# PennyMan_Ard_R3_Shield_v7.net
KiCad netlist of a schematic drawn in EAGLE
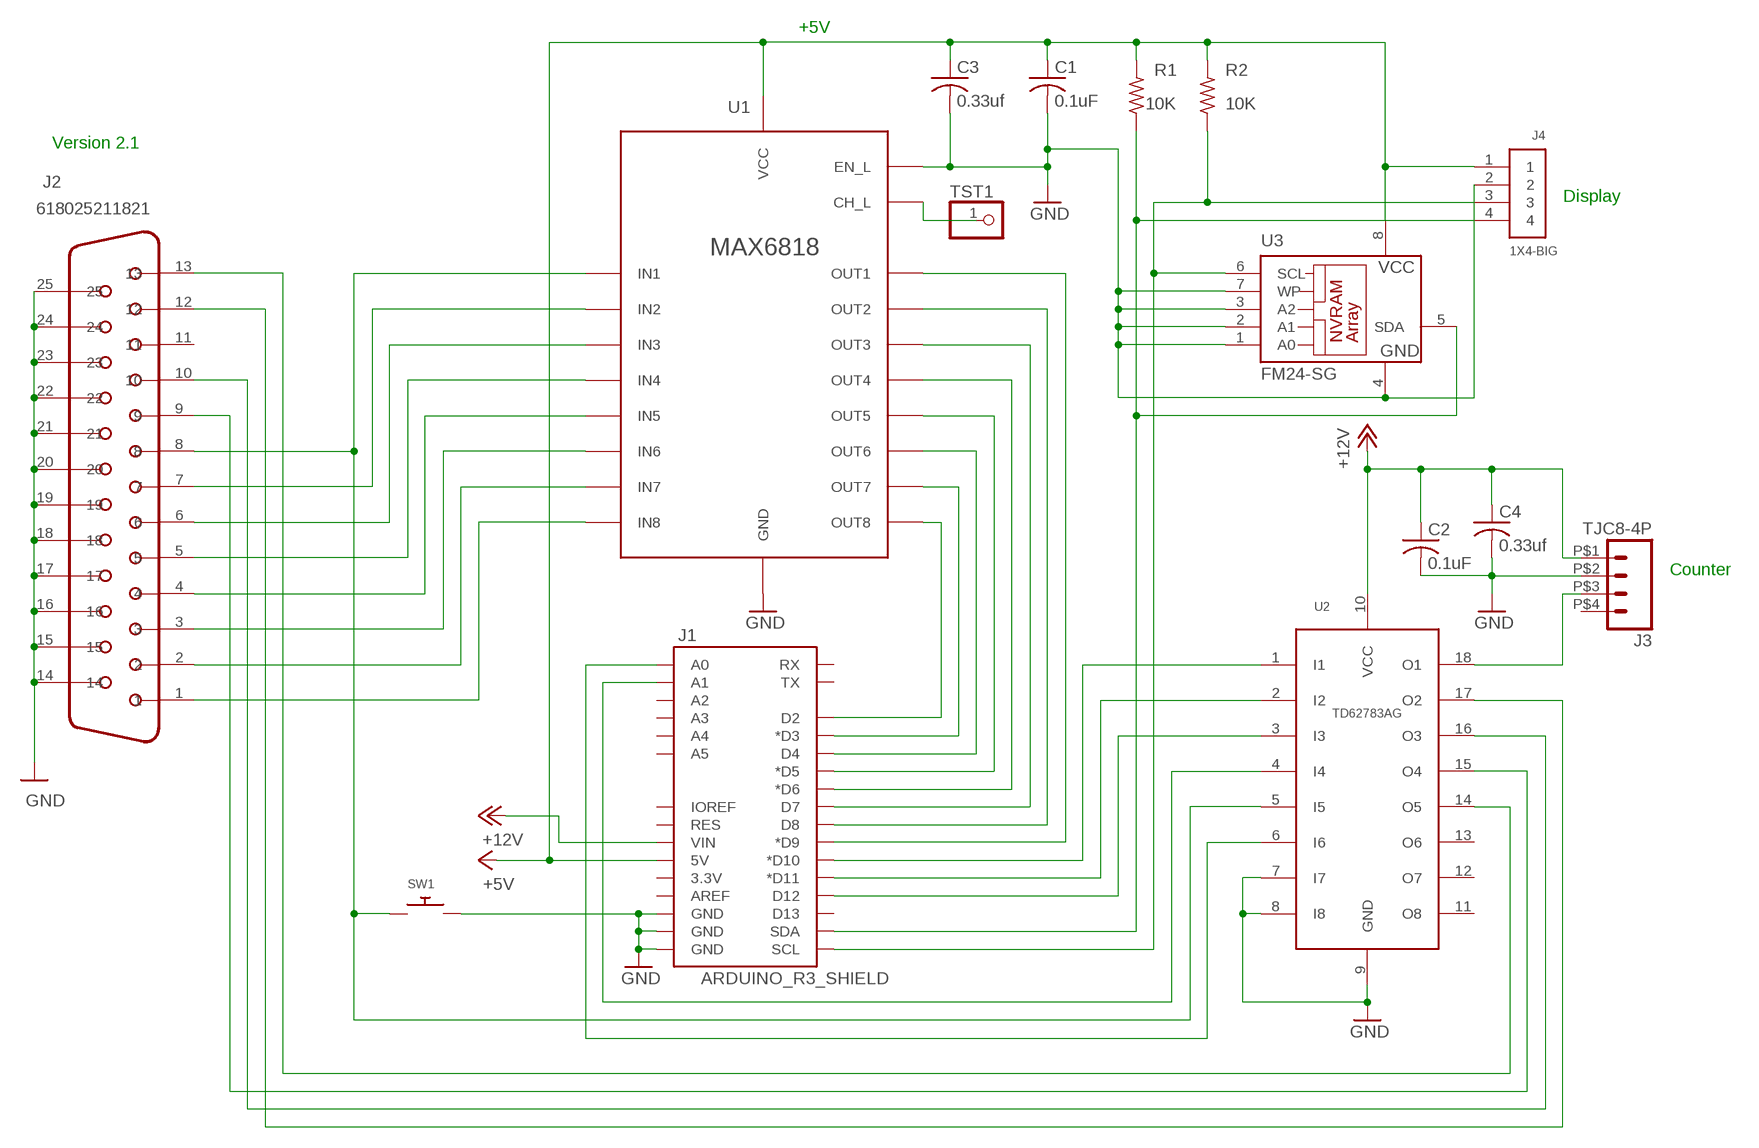
[diagram p0: schematic, sheet 1]

(export (version "E")
  (design (tool "Eeschema 10.0.6"))
  (components
    (comp (ref "C1")
      (value "0.1uF")
      (footprint "eagle-import:C0805")
      (libsource (lib "eagle-import") (part "C-USC0805"))
    )
    (comp (ref "C2")
      (value "0.1uF")
      (footprint "eagle-import:C0805")
      (libsource (lib "eagle-import") (part "C-USC0805"))
    )
    (comp (ref "C3")
      (value "0.33uf")
      (footprint "eagle-import:C1206")
      (libsource (lib "eagle-import") (part "C-USC1206"))
    )
    (comp (ref "C4")
      (value "0.33uf")
      (footprint "eagle-import:C1206")
      (libsource (lib "eagle-import") (part "C-USC1206"))
    )
    (comp (ref "J1")
      (value "ARDUINO_R3_SHIELD")
      (footprint "eagle-import:UNO_R3_SHIELD")
      (libsource (lib "eagle-import") (part "ARDUINO_R3_SHIELD"))
    )
    (comp (ref "J2")
      (value "618025211821")
      (footprint "eagle-import:618025211821")
      (libsource (lib "eagle-import") (part "618025211821"))
    )
    (comp (ref "J3")
      (value "TJC8-4P")
      (footprint "eagle-import:TJC8-4P")
      (libsource (lib "eagle-import") (part "TJC8-4P"))
    )
    (comp (ref "J4")
      (value "1X4-BIG")
      (footprint "eagle-import:1X04-BIG")
      (libsource (lib "eagle-import") (part "1X4-BIG"))
    )
    (comp (ref "R1")
      (value "10K")
      (footprint "eagle-import:R0805")
      (libsource (lib "eagle-import") (part "R-US_R0805"))
    )
    (comp (ref "R2")
      (value "10K")
      (footprint "eagle-import:R0805")
      (libsource (lib "eagle-import") (part "R-US_R0805"))
    )
    (comp (ref "SW1")
      (value "SWITCH_PUSHBUTTONEVQ-PE")
      (footprint "eagle-import:TACT_PANA-EVQ")
      (libsource (lib "eagle-import") (part "SWITCH_PUSHBUTTONEVQ-PE"))
    )
    (comp (ref "TST1")
      (value "PINHD-1X1")
      (footprint "eagle-import:1X01")
      (libsource (lib "eagle-import") (part "PINHD-1X1"))
    )
    (comp (ref "U1")
      (value "MAX6818")
      (footprint "eagle-import:SSOP20")
      (libsource (lib "eagle-import") (part "MAX6818"))
    )
    (comp (ref "U2")
      (value "TD62783AG")
      (footprint "eagle-import:SOP18")
      (libsource (lib "eagle-import") (part "TD62783AG"))
    )
    (comp (ref "U3")
      (value "FM24-SG")
      (footprint "eagle-import:SO8")
      (libsource (lib "eagle-import") (part "FM24-SG"))
    )
  )
  (nets
    (net (code "1") (name "+5V") (class "Default")
      (node (ref "C1") (pin "1") (pinfunction "1_1") (pintype "passive"))
      (node (ref "C3") (pin "1") (pinfunction "1_1") (pintype "passive"))
      (node (ref "J1") (pin "5V") (pinfunction "5V_5V") (pintype "bidirectional"))
      (node (ref "J4") (pin "1") (pinfunction "1_1") (pintype "bidirectional"))
      (node (ref "R1") (pin "2") (pinfunction "2_2") (pintype "passive"))
      (node (ref "R2") (pin "2") (pinfunction "2_2") (pintype "passive"))
      (node (ref "U1") (pin "VCC") (pinfunction "VCC_VCC") (pintype "bidirectional"))
      (node (ref "U3") (pin "8") (pinfunction "VCC_8") (pintype "power_in"))
    )
    (net (code "2") (name "+12V") (class "Default")
      (node (ref "C2") (pin "1") (pinfunction "1_1") (pintype "passive"))
      (node (ref "C4") (pin "1") (pinfunction "1_1") (pintype "passive"))
      (node (ref "J1") (pin "VIN") (pinfunction "VIN_VIN") (pintype "bidirectional"))
      (node (ref "J3") (pin "P$1") (pinfunction "1_P$1") (pintype "passive"))
      (node (ref "U2") (pin "10") (pinfunction "VCC_10") (pintype "bidirectional"))
    )
    (net (code "3") (name "GND") (class "Default")
      (node (ref "C1") (pin "2") (pinfunction "2_2") (pintype "passive"))
      (node (ref "C2") (pin "2") (pinfunction "2_2") (pintype "passive"))
      (node (ref "C3") (pin "2") (pinfunction "2_2") (pintype "passive"))
      (node (ref "C4") (pin "2") (pinfunction "2_2") (pintype "passive"))
      (node (ref "J1") (pin "GND@0") (pinfunction "GND_GND@0") (pintype "bidirectional"))
      (node (ref "J1") (pin "GND@1") (pinfunction "GND_GND@1") (pintype "bidirectional"))
      (node (ref "J1") (pin "GND@2") (pinfunction "GND_GND@2") (pintype "bidirectional"))
      (node (ref "J2") (pin "14") (pinfunction "14_14") (pintype "bidirectional"))
      (node (ref "J2") (pin "15") (pinfunction "15_15") (pintype "bidirectional"))
      (node (ref "J2") (pin "16") (pinfunction "16_16") (pintype "bidirectional"))
      (node (ref "J2") (pin "17") (pinfunction "17_17") (pintype "bidirectional"))
      (node (ref "J2") (pin "18") (pinfunction "18_18") (pintype "bidirectional"))
      (node (ref "J2") (pin "19") (pinfunction "19_19") (pintype "bidirectional"))
      (node (ref "J2") (pin "20") (pinfunction "20_20") (pintype "bidirectional"))
      (node (ref "J2") (pin "21") (pinfunction "21_21") (pintype "bidirectional"))
      (node (ref "J2") (pin "22") (pinfunction "22_22") (pintype "bidirectional"))
      (node (ref "J2") (pin "23") (pinfunction "23_23") (pintype "bidirectional"))
      (node (ref "J2") (pin "24") (pinfunction "24_24") (pintype "bidirectional"))
      (node (ref "J2") (pin "25") (pinfunction "25_25") (pintype "bidirectional"))
      (node (ref "J3") (pin "P$2") (pinfunction "2_P$2") (pintype "passive"))
      (node (ref "J4") (pin "2") (pinfunction "2_2") (pintype "bidirectional"))
      (node (ref "SW1") (pin "P$2") (pinfunction "P$2_P$2") (pintype "passive"))
      (node (ref "U1") (pin "EN_L") (pinfunction "EN_L_EN_L") (pintype "bidirectional"))
      (node (ref "U1") (pin "GND") (pinfunction "GND_GND") (pintype "bidirectional"))
      (node (ref "U2") (pin "7") (pinfunction "I7_7") (pintype "bidirectional"))
      (node (ref "U2") (pin "8") (pinfunction "I8_8") (pintype "bidirectional"))
      (node (ref "U2") (pin "9") (pinfunction "GND_9") (pintype "bidirectional"))
      (node (ref "U3") (pin "1") (pinfunction "A0_1") (pintype "passive"))
      (node (ref "U3") (pin "2") (pinfunction "A1_2") (pintype "passive"))
      (node (ref "U3") (pin "3") (pinfunction "A2_3") (pintype "passive"))
      (node (ref "U3") (pin "4") (pinfunction "GND_4") (pintype "power_in"))
      (node (ref "U3") (pin "7") (pinfunction "WP_7") (pintype "input"))
    )
    (net (code "4") (name "Net-(J1-*D3)") (class "Default")
      (node (ref "J1") (pin "D3") (pinfunction "*D3_D3") (pintype "bidirectional"))
      (node (ref "U1") (pin "OUT7") (pinfunction "OUT7_OUT7") (pintype "bidirectional"))
    )
    (net (code "5") (name "Net-(J1-*D5)") (class "Default")
      (node (ref "J1") (pin "D5") (pinfunction "*D5_D5") (pintype "bidirectional"))
      (node (ref "U1") (pin "OUT5") (pinfunction "OUT5_OUT5") (pintype "bidirectional"))
    )
    (net (code "6") (name "Net-(J1-*D6)") (class "Default")
      (node (ref "J1") (pin "D6") (pinfunction "*D6_D6") (pintype "bidirectional"))
      (node (ref "U1") (pin "OUT4") (pinfunction "OUT4_OUT4") (pintype "bidirectional"))
    )
    (net (code "7") (name "Net-(J1-*D9)") (class "Default")
      (node (ref "J1") (pin "D9") (pinfunction "*D9_D9") (pintype "bidirectional"))
      (node (ref "U1") (pin "OUT1") (pinfunction "OUT1_OUT1") (pintype "bidirectional"))
    )
    (net (code "8") (name "Net-(J1-*D10)") (class "Default")
      (node (ref "J1") (pin "D10") (pinfunction "*D10_D10") (pintype "bidirectional"))
      (node (ref "U2") (pin "1") (pinfunction "I1_1") (pintype "bidirectional"))
    )
    (net (code "9") (name "Net-(J1-*D11)") (class "Default")
      (node (ref "J1") (pin "D11") (pinfunction "*D11_D11") (pintype "bidirectional"))
      (node (ref "U2") (pin "2") (pinfunction "I2_2") (pintype "bidirectional"))
    )
    (net (code "10") (name "Net-(J1-PadD2)") (class "Default")
      (node (ref "J1") (pin "D2") (pinfunction "D2_D2") (pintype "bidirectional"))
      (node (ref "U1") (pin "OUT8") (pinfunction "OUT8_OUT8") (pintype "bidirectional"))
    )
    (net (code "11") (name "Net-(J1-PadD4)") (class "Default")
      (node (ref "J1") (pin "D4") (pinfunction "D4_D4") (pintype "bidirectional"))
      (node (ref "U1") (pin "OUT6") (pinfunction "OUT6_OUT6") (pintype "bidirectional"))
    )
    (net (code "12") (name "Net-(J1-PadD7)") (class "Default")
      (node (ref "J1") (pin "D7") (pinfunction "D7_D7") (pintype "bidirectional"))
      (node (ref "U1") (pin "OUT3") (pinfunction "OUT3_OUT3") (pintype "bidirectional"))
    )
    (net (code "13") (name "Net-(J1-PadD8)") (class "Default")
      (node (ref "J1") (pin "D8") (pinfunction "D8_D8") (pintype "bidirectional"))
      (node (ref "U1") (pin "OUT2") (pinfunction "OUT2_OUT2") (pintype "bidirectional"))
    )
    (net (code "14") (name "Net-(J2-Pad1)") (class "Default")
      (node (ref "J2") (pin "1") (pinfunction "1_1") (pintype "bidirectional"))
      (node (ref "U1") (pin "IN8") (pinfunction "IN8_IN8") (pintype "bidirectional"))
    )
    (net (code "15") (name "Net-(J2-Pad2)") (class "Default")
      (node (ref "J2") (pin "2") (pinfunction "2_2") (pintype "bidirectional"))
      (node (ref "U1") (pin "IN7") (pinfunction "IN7_IN7") (pintype "bidirectional"))
    )
    (net (code "16") (name "Net-(J2-Pad3)") (class "Default")
      (node (ref "J2") (pin "3") (pinfunction "3_3") (pintype "bidirectional"))
      (node (ref "U1") (pin "IN6") (pinfunction "IN6_IN6") (pintype "bidirectional"))
    )
    (net (code "17") (name "Net-(J2-Pad4)") (class "Default")
      (node (ref "J2") (pin "4") (pinfunction "4_4") (pintype "bidirectional"))
      (node (ref "U1") (pin "IN5") (pinfunction "IN5_IN5") (pintype "bidirectional"))
    )
    (net (code "18") (name "Net-(J2-Pad5)") (class "Default")
      (node (ref "J2") (pin "5") (pinfunction "5_5") (pintype "bidirectional"))
      (node (ref "U1") (pin "IN4") (pinfunction "IN4_IN4") (pintype "bidirectional"))
    )
    (net (code "19") (name "Net-(J2-Pad6)") (class "Default")
      (node (ref "J2") (pin "6") (pinfunction "6_6") (pintype "bidirectional"))
      (node (ref "U1") (pin "IN3") (pinfunction "IN3_IN3") (pintype "bidirectional"))
    )
    (net (code "20") (name "Net-(J2-Pad7)") (class "Default")
      (node (ref "J2") (pin "7") (pinfunction "7_7") (pintype "bidirectional"))
      (node (ref "U1") (pin "IN2") (pinfunction "IN2_IN2") (pintype "bidirectional"))
    )
    (net (code "21") (name "Net-(J3-3)") (class "Default")
      (node (ref "J3") (pin "P$3") (pinfunction "3_P$3") (pintype "passive"))
      (node (ref "U2") (pin "18") (pinfunction "O1_18") (pintype "bidirectional"))
    )
    (net (code "22") (name "Net-(TST1-Pad1)") (class "Default")
      (node (ref "TST1") (pin "1") (pinfunction "1_1") (pintype "passive"))
      (node (ref "U1") (pin "CH_L") (pinfunction "CH_L_CH_L") (pintype "bidirectional"))
    )
    (net (code "23") (name "Net-(U2-I3)") (class "Default")
      (node (ref "J1") (pin "D12") (pinfunction "D12_D12") (pintype "bidirectional"))
      (node (ref "U2") (pin "3") (pinfunction "I3_3") (pintype "bidirectional"))
    )
    (net (code "24") (name "Net-(U2-I4)") (class "Default")
      (node (ref "J1") (pin "A1") (pinfunction "A1_A1") (pintype "bidirectional"))
      (node (ref "U2") (pin "4") (pinfunction "I4_4") (pintype "bidirectional"))
    )
    (net (code "25") (name "Net-(U2-I5)") (class "Default")
      (node (ref "J2") (pin "8") (pinfunction "8_8") (pintype "bidirectional"))
      (node (ref "SW1") (pin "P$1") (pinfunction "P$1_P$1") (pintype "passive"))
      (node (ref "U1") (pin "IN1") (pinfunction "IN1_IN1") (pintype "bidirectional"))
      (node (ref "U2") (pin "5") (pinfunction "I5_5") (pintype "bidirectional"))
    )
    (net (code "26") (name "Net-(U2-I6)") (class "Default")
      (node (ref "J1") (pin "A0") (pinfunction "A0_A0") (pintype "bidirectional"))
      (node (ref "U2") (pin "6") (pinfunction "I6_6") (pintype "bidirectional"))
    )
    (net (code "27") (name "Net-(U2-O2)") (class "Default")
      (node (ref "J2") (pin "12") (pinfunction "12_12") (pintype "bidirectional"))
      (node (ref "U2") (pin "17") (pinfunction "O2_17") (pintype "bidirectional"))
    )
    (net (code "28") (name "Net-(U2-O3)") (class "Default")
      (node (ref "J2") (pin "10") (pinfunction "10_10") (pintype "bidirectional"))
      (node (ref "U2") (pin "16") (pinfunction "O3_16") (pintype "bidirectional"))
    )
    (net (code "29") (name "Net-(U2-O4)") (class "Default")
      (node (ref "J2") (pin "9") (pinfunction "9_9") (pintype "bidirectional"))
      (node (ref "U2") (pin "15") (pinfunction "O4_15") (pintype "bidirectional"))
    )
    (net (code "30") (name "Net-(U2-O5)") (class "Default")
      (node (ref "J2") (pin "13") (pinfunction "13_13") (pintype "bidirectional"))
      (node (ref "U2") (pin "14") (pinfunction "O5_14") (pintype "bidirectional"))
    )
    (net (code "31") (name "Net-(U3-SCL)") (class "Default")
      (node (ref "J1") (pin "SCL") (pinfunction "SCL_SCL") (pintype "bidirectional"))
      (node (ref "J4") (pin "3") (pinfunction "3_3") (pintype "bidirectional"))
      (node (ref "R2") (pin "1") (pinfunction "1_1") (pintype "passive"))
      (node (ref "U3") (pin "6") (pinfunction "SCL_6") (pintype "input"))
    )
    (net (code "32") (name "Net-(U3-SDA)") (class "Default")
      (node (ref "J1") (pin "SDA") (pinfunction "SDA_SDA") (pintype "bidirectional"))
      (node (ref "J4") (pin "4") (pinfunction "4_4") (pintype "bidirectional"))
      (node (ref "R1") (pin "1") (pinfunction "1_1") (pintype "passive"))
      (node (ref "U3") (pin "5") (pinfunction "SDA_5") (pintype "bidirectional"))
    )
    (net (code "33") (name "unconnected-(J1-Pad3.3V)") (class "Default")
      (node (ref "J1") (pin "3.3V") (pinfunction "3.3V_3.3V") (pintype "bidirectional"))
    )
    (net (code "34") (name "unconnected-(J1-PadA2)") (class "Default")
      (node (ref "J1") (pin "A2") (pinfunction "A2_A2") (pintype "bidirectional"))
    )
    (net (code "35") (name "unconnected-(J1-PadA3)") (class "Default")
      (node (ref "J1") (pin "A3") (pinfunction "A3_A3") (pintype "bidirectional"))
    )
    (net (code "36") (name "unconnected-(J1-PadA4)") (class "Default")
      (node (ref "J1") (pin "A4") (pinfunction "A4_A4") (pintype "bidirectional"))
    )
    (net (code "37") (name "unconnected-(J1-PadA5)") (class "Default")
      (node (ref "J1") (pin "A5") (pinfunction "A5_A5") (pintype "bidirectional"))
    )
    (net (code "38") (name "unconnected-(J1-PadAREF)") (class "Default")
      (node (ref "J1") (pin "AREF") (pinfunction "AREF_AREF") (pintype "bidirectional"))
    )
    (net (code "39") (name "unconnected-(J1-PadD13)") (class "Default")
      (node (ref "J1") (pin "D13") (pinfunction "D13_D13") (pintype "bidirectional"))
    )
    (net (code "40") (name "unconnected-(J1-PadIOREF)") (class "Default")
      (node (ref "J1") (pin "IOREF") (pinfunction "IOREF_IOREF") (pintype "bidirectional"))
    )
    (net (code "41") (name "unconnected-(J1-PadRES)") (class "Default")
      (node (ref "J1") (pin "RES") (pinfunction "RES_RES") (pintype "bidirectional"))
    )
    (net (code "42") (name "unconnected-(J1-PadRX)") (class "Default")
      (node (ref "J1") (pin "RX") (pinfunction "RX_RX") (pintype "bidirectional"))
    )
    (net (code "43") (name "unconnected-(J1-PadTX)") (class "Default")
      (node (ref "J1") (pin "TX") (pinfunction "TX_TX") (pintype "bidirectional"))
    )
    (net (code "44") (name "unconnected-(J2-Pad11)") (class "Default")
      (node (ref "J2") (pin "11") (pinfunction "11_11") (pintype "bidirectional"))
    )
    (net (code "45") (name "unconnected-(J3-4-PadP$4)") (class "Default")
      (node (ref "J3") (pin "P$4") (pinfunction "4_P$4") (pintype "passive"))
    )
    (net (code "46") (name "unconnected-(U2-O6-Pad13)") (class "Default")
      (node (ref "U2") (pin "13") (pinfunction "O6_13") (pintype "bidirectional"))
    )
    (net (code "47") (name "unconnected-(U2-O7-Pad12)") (class "Default")
      (node (ref "U2") (pin "12") (pinfunction "O7_12") (pintype "bidirectional"))
    )
    (net (code "48") (name "unconnected-(U2-O8-Pad11)") (class "Default")
      (node (ref "U2") (pin "11") (pinfunction "O8_11") (pintype "bidirectional"))
    )
  )
)
